# Main.net
KiCad netlist of a schematic drawn in Altium Designer
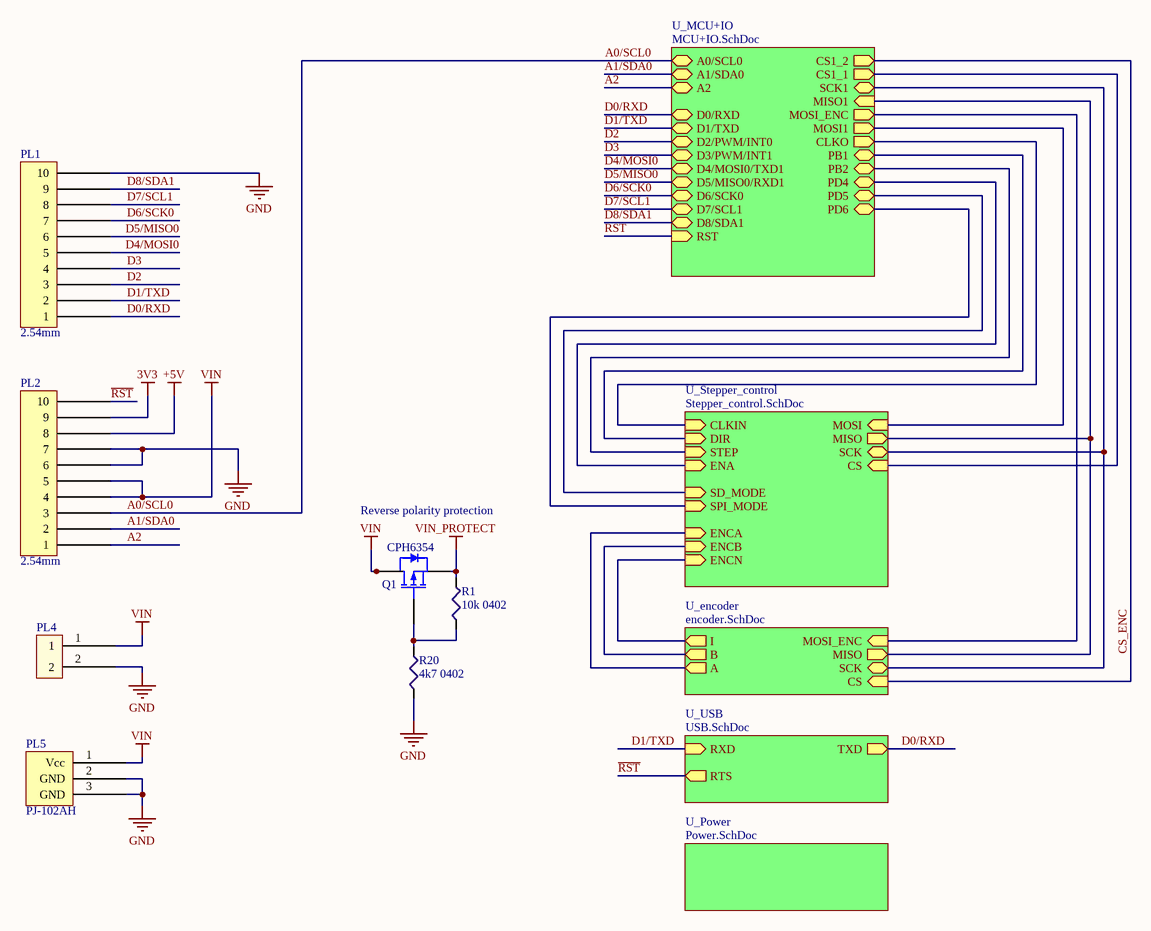
[diagram p0: Main.SchDoc]

(export (version "E")
  (design (tool "Eeschema 10.0.6"))
  (components
    (comp (ref "PL1")
      (value "2.54mm")
      (footprint "10-pin female 2.54mm")
      (description "Pin header 10-pin 2.54mm female")
      (fields (field (name "MFG. PART NUMBER") "DS1023-1*10S21"))
      (libsource (lib "ON Development Vault") (part "10-pin header"))
    )
    (comp (ref "PL2")
      (value "2.54mm")
      (footprint "10-pin female 2.54mm")
      (description "Pin header 10-pin 2.54mm female")
      (fields (field (name "MFG. PART NUMBER") "DS1023-1*10S21"))
      (libsource (lib "ON Development Vault") (part "10-pin header"))
    )
    (comp (ref "PL4")
      (value "2pin Terminal block 5.08mm")
      (footprint "5mm header")
      (description "PCB terminal block, angled 90°; 5mm, 2-way, 1.5mm2")
      (fields (field (name "MFG. PART NUMBER") "DG301-5.0-02P-11-00A(H)"))
      (libsource (lib "ON Development Vault") (part "Header 2-way"))
    )
    (comp (ref "PL5")
      (value "PJ-102AH")
      (footprint "PJ-102AH")
      (description "CONN PWR JACK 2X5.5MM SOLDER")
      (libsource (lib "ON Development Vault") (part "PJ-102AH"))
    )
    (comp (ref "Q1")
      (value "CPH6354")
      (footprint "SOT95P280X95-6N")
      (description "MOSFET P-CH 60V 4A CPH6")
      (fields (field (name "MFG. PART NUMBER") "CPH6354-TL-W"))
      (libsource (lib "ON Development Vault") (part "P-channel CPH6354"))
    )
    (comp (ref "R1")
      (value "10k 0402")
      (footprint "RES_0402")
      (description "RES SMD 10K OHM 1% 1/16W 0402")
      (fields (field (name "POWER") "1/16 W") (field (name "TOLERANCE") "1 %"))
      (libsource (lib "ON Development Vault") (part "Resistor"))
    )
    (comp (ref "R20")
      (value "4k7 0402")
      (footprint "RES_0402")
      (description "RES SMD 4.7K OHM 1% 1/16W 0402")
      (fields (field (name "POWER") "1/16W") (field (name "TOLERANCE") "1"))
      (libsource (lib "ON Development Vault") (part "Resistor"))
    )
  )
  (nets
    (net (code "1") (name "+5V") (class "Default")
      (node (ref "PL2") (pin "8") (pinfunction "8_8") (pintype "passive"))
    )
    (net (code "3") (name "/A0{slash}SCL0") (class "Default")
      (node (ref "PL2") (pin "3") (pinfunction "3_3") (pintype "passive"))
    )
    (net (code "4") (name "/A1{slash}SDA0") (class "Default")
      (node (ref "PL2") (pin "2") (pinfunction "2_2") (pintype "passive"))
    )
    (net (code "5") (name "/A2") (class "Default")
      (node (ref "PL2") (pin "1") (pinfunction "1_1") (pintype "passive"))
    )
    (net (code "10") (name "/D0{slash}RXD") (class "Default")
      (node (ref "PL1") (pin "1") (pinfunction "1_1") (pintype "passive"))
    )
    (net (code "11") (name "/D1{slash}TXD") (class "Default")
      (node (ref "PL1") (pin "2") (pinfunction "2_2") (pintype "passive"))
    )
    (net (code "12") (name "/D2") (class "Default")
      (node (ref "PL1") (pin "3") (pinfunction "3_3") (pintype "passive"))
    )
    (net (code "13") (name "/D3") (class "Default")
      (node (ref "PL1") (pin "4") (pinfunction "4_4") (pintype "passive"))
    )
    (net (code "14") (name "/D4{slash}MOSI0") (class "Default")
      (node (ref "PL1") (pin "5") (pinfunction "5_5") (pintype "passive"))
    )
    (net (code "15") (name "/D5{slash}MISO0") (class "Default")
      (node (ref "PL1") (pin "6") (pinfunction "6_6") (pintype "passive"))
    )
    (net (code "16") (name "/D6{slash}SCK0") (class "Default")
      (node (ref "PL1") (pin "7") (pinfunction "7_7") (pintype "passive"))
    )
    (net (code "17") (name "/D7{slash}SCL1") (class "Default")
      (node (ref "PL1") (pin "8") (pinfunction "8_8") (pintype "passive"))
    )
    (net (code "18") (name "/D8{slash}SDA1") (class "Default")
      (node (ref "PL1") (pin "9") (pinfunction "9_9") (pintype "passive"))
    )
    (net (code "29") (name "/~{RST}") (class "Default")
      (node (ref "PL2") (pin "10") (pinfunction "10_10") (pintype "passive"))
    )
    (net (code "30") (name "3V3") (class "Default")
      (node (ref "PL2") (pin "9") (pinfunction "9_9") (pintype "passive"))
    )
    (net (code "31") (name "GND") (class "Default")
      (node (ref "PL1") (pin "10") (pinfunction "10_10") (pintype "passive"))
      (node (ref "PL2") (pin "6") (pinfunction "6_6") (pintype "passive"))
      (node (ref "PL2") (pin "7") (pinfunction "7_7") (pintype "passive"))
      (node (ref "PL4") (pin "2") (pinfunction "2_2") (pintype "passive"))
      (node (ref "PL5") (pin "2") (pinfunction "GND_2") (pintype "passive"))
      (node (ref "PL5") (pin "3") (pinfunction "GND_3") (pintype "passive"))
      (node (ref "R20") (pin "1") (pinfunction "1_1") (pintype "passive"))
    )
    (net (code "32") (name "Net-(Q1-GATE)") (class "Default")
      (node (ref "Q1") (pin "3") (pinfunction "GATE_3") (pintype "passive"))
      (node (ref "R1") (pin "1") (pinfunction "1_1") (pintype "passive"))
      (node (ref "R20") (pin "2") (pinfunction "2_2") (pintype "passive"))
    )
    (net (code "33") (name "VIN") (class "Default")
      (node (ref "PL2") (pin "4") (pinfunction "4_4") (pintype "passive"))
      (node (ref "PL2") (pin "5") (pinfunction "5_5") (pintype "passive"))
      (node (ref "PL4") (pin "1") (pinfunction "1_1") (pintype "passive"))
      (node (ref "PL5") (pin "1") (pinfunction "Vcc_1") (pintype "passive"))
      (node (ref "Q1") (pin "1") (pinfunction "DRAIN_1") (pintype "passive"))
      (node (ref "Q1") (pin "2") (pinfunction "DRAIN_2") (pintype "passive"))
      (node (ref "Q1") (pin "5") (pinfunction "DRAIN_5") (pintype "passive"))
      (node (ref "Q1") (pin "6") (pinfunction "DRAIN_6") (pintype "passive"))
    )
    (net (code "34") (name "VIN_PROTECT") (class "Default")
      (node (ref "Q1") (pin "4") (pinfunction "SOURCE_4") (pintype "passive"))
      (node (ref "R1") (pin "2") (pinfunction "2_2") (pintype "passive"))
    )
  )
)
